# SolderIron2_0.net
KiCad netlist of a schematic drawn in EAGLE
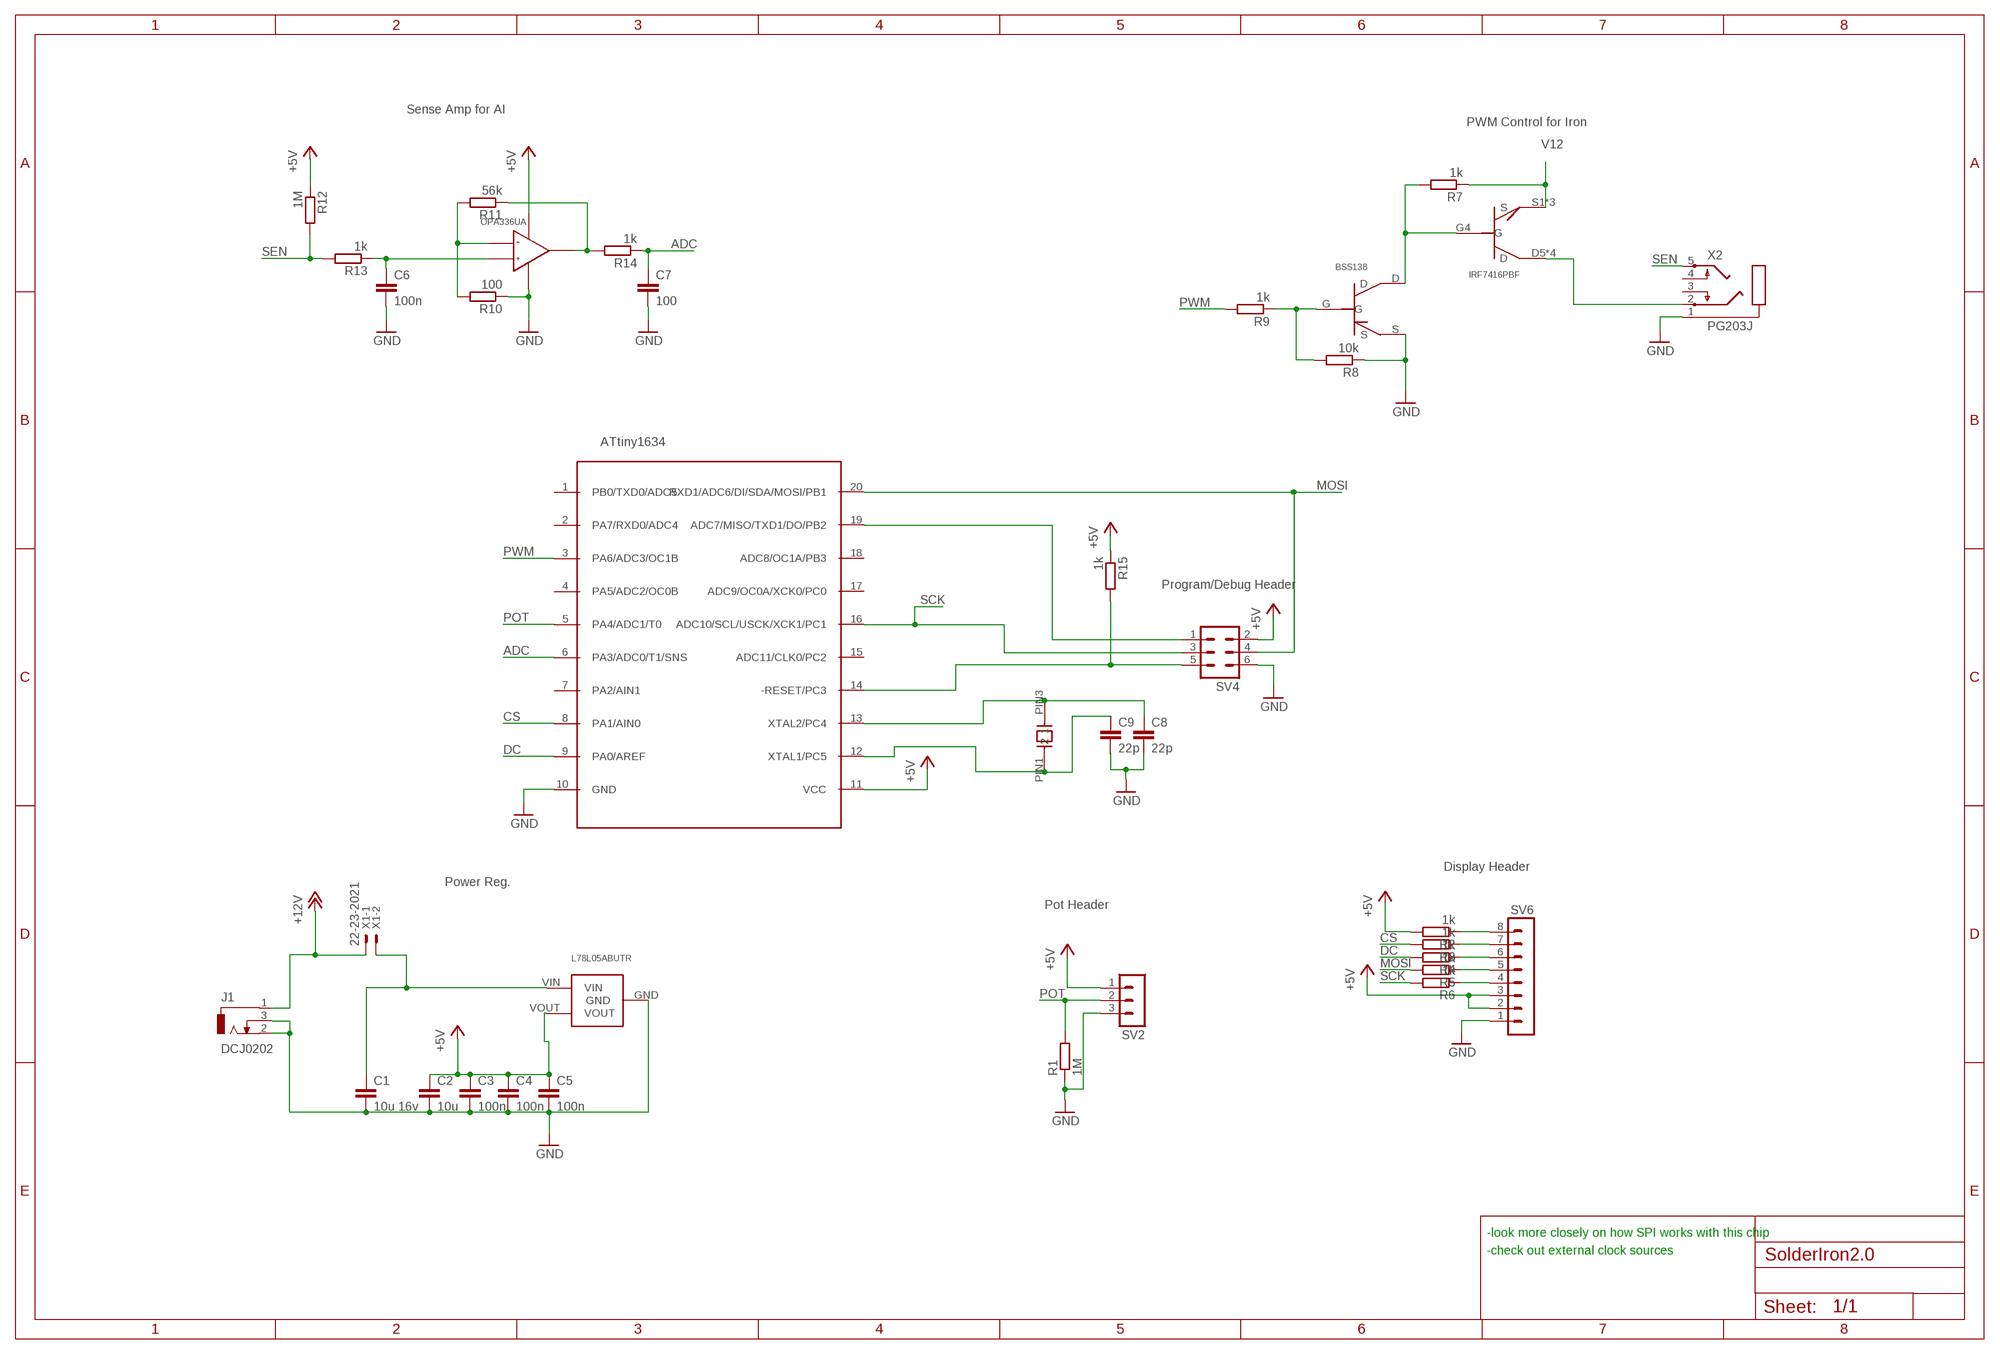
[diagram p0: schematic, sheet 1]

(export (version "E")
  (design (tool "Eeschema 10.0.6"))
  (components
    (comp (ref "C1")
      (value "10u 16v")
      (footprint "eagle-import:C1206")
      (libsource (lib "eagle-import") (part "CC1206"))
    )
    (comp (ref "C2")
      (value "10u")
      (footprint "eagle-import:C1206")
      (libsource (lib "eagle-import") (part "CC1206"))
    )
    (comp (ref "C3")
      (value "100n")
      (footprint "eagle-import:C1206")
      (libsource (lib "eagle-import") (part "CC1206"))
    )
    (comp (ref "C4")
      (value "100n")
      (footprint "eagle-import:C1206")
      (libsource (lib "eagle-import") (part "CC1206"))
    )
    (comp (ref "C5")
      (value "100n")
      (footprint "eagle-import:C1206")
      (libsource (lib "eagle-import") (part "CC1206"))
    )
    (comp (ref "C6")
      (value "100n")
      (footprint "eagle-import:C1206")
      (libsource (lib "eagle-import") (part "CC1206"))
    )
    (comp (ref "C7")
      (value "100")
      (footprint "eagle-import:C1206")
      (libsource (lib "eagle-import") (part "CC1206"))
    )
    (comp (ref "C8")
      (value "22p")
      (footprint "eagle-import:C1206")
      (libsource (lib "eagle-import") (part "CC1206"))
    )
    (comp (ref "C9")
      (value "22p")
      (footprint "eagle-import:C1206")
      (libsource (lib "eagle-import") (part "CC1206"))
    )
    (comp (ref "J1")
      (value "DCJ0202")
      (footprint "eagle-import:POWERJACK2.1MM")
      (libsource (lib "eagle-import") (part "DCJ0202"))
    )
    (comp (ref "R1")
      (value "1M")
      (footprint "eagle-import:R0603")
      (libsource (lib "eagle-import") (part "RR0603"))
    )
    (comp (ref "R2")
      (value "1k")
      (footprint "eagle-import:R0603")
      (libsource (lib "eagle-import") (part "RR0603"))
    )
    (comp (ref "R3")
      (value "1k")
      (footprint "eagle-import:R0603")
      (libsource (lib "eagle-import") (part "RR0603"))
    )
    (comp (ref "R4")
      (value "1k")
      (footprint "eagle-import:R0603")
      (libsource (lib "eagle-import") (part "RR0603"))
    )
    (comp (ref "R5")
      (value "1k")
      (footprint "eagle-import:R0603")
      (libsource (lib "eagle-import") (part "RR0603"))
    )
    (comp (ref "R6")
      (value "1k")
      (footprint "eagle-import:R0603")
      (libsource (lib "eagle-import") (part "RR0603"))
    )
    (comp (ref "R7")
      (value "1k")
      (footprint "eagle-import:R0603")
      (libsource (lib "eagle-import") (part "RR0603"))
    )
    (comp (ref "R8")
      (value "10k")
      (footprint "eagle-import:R0603")
      (libsource (lib "eagle-import") (part "RR0603"))
    )
    (comp (ref "R9")
      (value "1k")
      (footprint "eagle-import:R0603")
      (libsource (lib "eagle-import") (part "RR0603"))
    )
    (comp (ref "R10")
      (value "100")
      (footprint "eagle-import:R0603")
      (libsource (lib "eagle-import") (part "RR0603"))
    )
    (comp (ref "R11")
      (value "56k")
      (footprint "eagle-import:R0603")
      (libsource (lib "eagle-import") (part "RR0603"))
    )
    (comp (ref "R12")
      (value "1M")
      (footprint "eagle-import:R0603")
      (libsource (lib "eagle-import") (part "RR0603"))
    )
    (comp (ref "R13")
      (value "1k")
      (footprint "eagle-import:R0603")
      (libsource (lib "eagle-import") (part "RR0603"))
    )
    (comp (ref "R14")
      (value "1k")
      (footprint "eagle-import:R0603")
      (libsource (lib "eagle-import") (part "RR0603"))
    )
    (comp (ref "R15")
      (value "1k")
      (footprint "eagle-import:R0603")
      (libsource (lib "eagle-import") (part "RR0603"))
    )
    (comp (ref "SV2")
      (value "MA03-1")
      (footprint "eagle-import:MA03-1")
      (libsource (lib "eagle-import") (part "MA03-1"))
    )
    (comp (ref "SV4")
      (value "MA03-2")
      (footprint "eagle-import:MA03-2")
      (libsource (lib "eagle-import") (part "MA03-2"))
    )
    (comp (ref "SV6")
      (value "MA08-1")
      (footprint "eagle-import:MA08-1")
      (libsource (lib "eagle-import") (part "MA08-1"))
    )
    (comp (ref "U$1")
      (value "IRF7416PBF")
      (footprint "eagle-import:8-SOIC")
      (libsource (lib "eagle-import") (part "IRF7416PBF"))
    )
    (comp (ref "U$2")
      (value "L78L05ABUTR")
      (footprint "eagle-import:SOT89-3")
      (libsource (lib "eagle-import") (part "L78L05ABUTR"))
    )
    (comp (ref "U$3")
      (value "BSS138")
      (footprint "eagle-import:SOT-23")
      (libsource (lib "eagle-import") (part "BSS138"))
    )
    (comp (ref "U$4")
      (value "OPA336UA")
      (footprint "eagle-import:8-SOIC")
      (libsource (lib "eagle-import") (part "OPA336UA"))
    )
    (comp (ref "U$5")
      (value "ATTINY1634")
      (footprint "eagle-import:SOIC20")
      (libsource (lib "eagle-import") (part "ATTINY1634"))
    )
    (comp (ref "U$6")
      (value "CX3225GB12000H0KPSC1")
      (footprint "eagle-import:4-SIZ")
      (libsource (lib "eagle-import") (part "CX3225GB12000H0KPSC1"))
    )
    (comp (ref "X1")
      (value "22-23-2021")
      (footprint "eagle-import:22-23-2021")
      (fields (field (name "MF") "MOLEX"))
      (libsource (lib "eagle-import") (part "22-23-2021"))
    )
    (comp (ref "X2")
      (value "PG203J")
      (footprint "eagle-import:PG203J")
      (libsource (lib "eagle-import") (part "PG203J"))
    )
  )
  (nets
    (net (code "1") (name "+5V") (class "Default")
      (node (ref "C2") (pin "1") (pinfunction "1_1") (pintype "passive"))
      (node (ref "C3") (pin "1") (pinfunction "1_1") (pintype "passive"))
      (node (ref "C4") (pin "1") (pinfunction "1_1") (pintype "passive"))
      (node (ref "C5") (pin "1") (pinfunction "1_1") (pintype "passive"))
      (node (ref "R12") (pin "1") (pinfunction "1_1") (pintype "passive"))
      (node (ref "R15") (pin "1") (pinfunction "1_1") (pintype "passive"))
      (node (ref "R2") (pin "2") (pinfunction "2_2") (pintype "passive"))
      (node (ref "SV2") (pin "1") (pinfunction "1_1") (pintype "passive"))
      (node (ref "SV4") (pin "2") (pinfunction "2_2") (pintype "passive"))
      (node (ref "SV6") (pin "2") (pinfunction "2_2") (pintype "passive"))
      (node (ref "SV6") (pin "3") (pinfunction "3_3") (pintype "passive"))
      (node (ref "U$2") (pin "VOUT") (pinfunction "VOUT_VOUT") (pintype "bidirectional"))
      (node (ref "U$4") (pin "D7") (pinfunction "V+_D7") (pintype "bidirectional"))
      (node (ref "U$5") (pin "11") (pinfunction "VCC_11") (pintype "power_in"))
    )
    (net (code "2") (name "+12V") (class "Default")
      (node (ref "J1") (pin "1") (pinfunction "1_1") (pintype "passive"))
      (node (ref "X1") (pin "1") (pinfunction "S_1") (pintype "passive"))
    )
    (net (code "3") (name "/ADC") (class "Default")
      (node (ref "C7") (pin "1") (pinfunction "1_1") (pintype "passive"))
      (node (ref "R14") (pin "1") (pinfunction "1_1") (pintype "passive"))
      (node (ref "U$5") (pin "6") (pinfunction "PA3/ADC0/T1/SNS_6") (pintype "bidirectional"))
    )
    (net (code "4") (name "/CS") (class "Default")
      (node (ref "R3") (pin "2") (pinfunction "2_2") (pintype "passive"))
      (node (ref "U$5") (pin "8") (pinfunction "PA1/AIN0_8") (pintype "bidirectional"))
    )
    (net (code "5") (name "/DC") (class "Default")
      (node (ref "R4") (pin "2") (pinfunction "2_2") (pintype "passive"))
      (node (ref "U$5") (pin "9") (pinfunction "PA0/AREF_9") (pintype "bidirectional"))
    )
    (net (code "6") (name "/MOSI") (class "Default")
      (node (ref "R5") (pin "2") (pinfunction "2_2") (pintype "passive"))
      (node (ref "SV4") (pin "4") (pinfunction "4_4") (pintype "passive"))
      (node (ref "U$5") (pin "20") (pinfunction "RXD1/ADC6/DI/SDA/MOSI/PB1_20") (pintype "bidirectional"))
    )
    (net (code "7") (name "/POT") (class "Default")
      (node (ref "R1") (pin "2") (pinfunction "2_2") (pintype "passive"))
      (node (ref "SV2") (pin "2") (pinfunction "2_2") (pintype "passive"))
      (node (ref "U$5") (pin "5") (pinfunction "PA4/ADC1/T0_5") (pintype "bidirectional"))
    )
    (net (code "8") (name "/PWM") (class "Default")
      (node (ref "R9") (pin "2") (pinfunction "2_2") (pintype "passive"))
      (node (ref "U$5") (pin "3") (pinfunction "PA6/ADC3/OC1B_3") (pintype "bidirectional"))
    )
    (net (code "9") (name "/SCK") (class "Default")
      (node (ref "R6") (pin "2") (pinfunction "2_2") (pintype "passive"))
      (node (ref "SV4") (pin "3") (pinfunction "3_3") (pintype "passive"))
      (node (ref "U$5") (pin "16") (pinfunction "ADC10/SCL/USCK/XCK1/PC1_16") (pintype "bidirectional"))
    )
    (net (code "10") (name "/SEN") (class "Default")
      (node (ref "R12") (pin "2") (pinfunction "2_2") (pintype "passive"))
      (node (ref "R13") (pin "2") (pinfunction "2_2") (pintype "passive"))
      (node (ref "X2") (pin "5") (pinfunction "5_5") (pintype "passive"))
    )
    (net (code "11") (name "/V12") (class "Default")
      (node (ref "C1") (pin "1") (pinfunction "1_1") (pintype "passive"))
      (node (ref "R7") (pin "1") (pinfunction "1_1") (pintype "passive"))
      (node (ref "U$1") (pin "S1") (pinfunction "S_S1") (pintype "bidirectional"))
      (node (ref "U$1") (pin "S2") (pinfunction "S_S2") (pintype "bidirectional"))
      (node (ref "U$1") (pin "S3") (pinfunction "S_S3") (pintype "bidirectional"))
      (node (ref "U$2") (pin "VIN") (pinfunction "VIN_VIN") (pintype "bidirectional"))
      (node (ref "X1") (pin "2") (pinfunction "S_2") (pintype "passive"))
    )
    (net (code "12") (name "GND") (class "Default")
      (node (ref "C1") (pin "2") (pinfunction "2_2") (pintype "passive"))
      (node (ref "C2") (pin "2") (pinfunction "2_2") (pintype "passive"))
      (node (ref "C3") (pin "2") (pinfunction "2_2") (pintype "passive"))
      (node (ref "C4") (pin "2") (pinfunction "2_2") (pintype "passive"))
      (node (ref "C5") (pin "2") (pinfunction "2_2") (pintype "passive"))
      (node (ref "C6") (pin "2") (pinfunction "2_2") (pintype "passive"))
      (node (ref "C7") (pin "2") (pinfunction "2_2") (pintype "passive"))
      (node (ref "C8") (pin "2") (pinfunction "2_2") (pintype "passive"))
      (node (ref "C9") (pin "2") (pinfunction "2_2") (pintype "passive"))
      (node (ref "J1") (pin "2") (pinfunction "3_2") (pintype "passive"))
      (node (ref "J1") (pin "3") (pinfunction "2_3") (pintype "passive"))
      (node (ref "R1") (pin "1") (pinfunction "1_1") (pintype "passive"))
      (node (ref "R10") (pin "1") (pinfunction "1_1") (pintype "passive"))
      (node (ref "R8") (pin "1") (pinfunction "1_1") (pintype "passive"))
      (node (ref "SV2") (pin "3") (pinfunction "3_3") (pintype "passive"))
      (node (ref "SV4") (pin "6") (pinfunction "6_6") (pintype "passive"))
      (node (ref "SV6") (pin "1") (pinfunction "1_1") (pintype "passive"))
      (node (ref "U$2") (pin "GND") (pinfunction "GND_GND") (pintype "bidirectional"))
      (node (ref "U$3") (pin "S") (pinfunction "S_S") (pintype "bidirectional"))
      (node (ref "U$4") (pin "G4") (pinfunction "V-_G4") (pintype "bidirectional"))
      (node (ref "U$5") (pin "10") (pinfunction "GND_10") (pintype "power_in"))
      (node (ref "X2") (pin "1") (pinfunction "1_1") (pintype "passive"))
    )
    (net (code "13") (name "Net-(R2-Pad1)") (class "Default")
      (node (ref "R2") (pin "1") (pinfunction "1_1") (pintype "passive"))
      (node (ref "SV6") (pin "8") (pinfunction "8_8") (pintype "passive"))
    )
    (net (code "14") (name "Net-(R3-Pad1)") (class "Default")
      (node (ref "R3") (pin "1") (pinfunction "1_1") (pintype "passive"))
      (node (ref "SV6") (pin "7") (pinfunction "7_7") (pintype "passive"))
    )
    (net (code "15") (name "Net-(R4-Pad1)") (class "Default")
      (node (ref "R4") (pin "1") (pinfunction "1_1") (pintype "passive"))
      (node (ref "SV6") (pin "6") (pinfunction "6_6") (pintype "passive"))
    )
    (net (code "16") (name "Net-(R5-Pad1)") (class "Default")
      (node (ref "R5") (pin "1") (pinfunction "1_1") (pintype "passive"))
      (node (ref "SV6") (pin "5") (pinfunction "5_5") (pintype "passive"))
    )
    (net (code "17") (name "Net-(R6-Pad1)") (class "Default")
      (node (ref "R6") (pin "1") (pinfunction "1_1") (pintype "passive"))
      (node (ref "SV6") (pin "4") (pinfunction "4_4") (pintype "passive"))
    )
    (net (code "18") (name "Net-(R8-Pad2)") (class "Default")
      (node (ref "R8") (pin "2") (pinfunction "2_2") (pintype "passive"))
      (node (ref "R9") (pin "1") (pinfunction "1_1") (pintype "passive"))
      (node (ref "U$3") (pin "G") (pinfunction "G_G") (pintype "bidirectional"))
    )
    (net (code "19") (name "Net-(U$1-D-PadD5)") (class "Default")
      (node (ref "U$1") (pin "D5") (pinfunction "D_D5") (pintype "bidirectional"))
      (node (ref "U$1") (pin "D6") (pinfunction "D_D6") (pintype "bidirectional"))
      (node (ref "U$1") (pin "D7") (pinfunction "D_D7") (pintype "bidirectional"))
      (node (ref "U$1") (pin "D8") (pinfunction "D_D8") (pintype "bidirectional"))
      (node (ref "X2") (pin "2") (pinfunction "2_2") (pintype "passive"))
    )
    (net (code "20") (name "Net-(U$1-G)") (class "Default")
      (node (ref "R7") (pin "2") (pinfunction "2_2") (pintype "passive"))
      (node (ref "U$1") (pin "G4") (pinfunction "G_G4") (pintype "bidirectional"))
      (node (ref "U$3") (pin "D") (pinfunction "D_D") (pintype "bidirectional"))
    )
    (net (code "21") (name "Net-(U$4-IN+)") (class "Default")
      (node (ref "C6") (pin "1") (pinfunction "1_1") (pintype "passive"))
      (node (ref "R13") (pin "1") (pinfunction "1_1") (pintype "passive"))
      (node (ref "U$4") (pin "S3") (pinfunction "IN+_S3") (pintype "bidirectional"))
    )
    (net (code "22") (name "Net-(U$4-IN-)") (class "Default")
      (node (ref "R10") (pin "2") (pinfunction "2_2") (pintype "passive"))
      (node (ref "R11") (pin "2") (pinfunction "2_2") (pintype "passive"))
      (node (ref "U$4") (pin "S2") (pinfunction "IN-_S2") (pintype "bidirectional"))
    )
    (net (code "23") (name "Net-(U$4-OUTPUT)") (class "Default")
      (node (ref "R11") (pin "1") (pinfunction "1_1") (pintype "passive"))
      (node (ref "R14") (pin "2") (pinfunction "2_2") (pintype "passive"))
      (node (ref "U$4") (pin "D6") (pinfunction "OUTPUT_D6") (pintype "bidirectional"))
    )
    (net (code "24") (name "Net-(U$5--RESET{slash}PC3)") (class "Default")
      (node (ref "R15") (pin "2") (pinfunction "2_2") (pintype "passive"))
      (node (ref "SV4") (pin "5") (pinfunction "5_5") (pintype "passive"))
      (node (ref "U$5") (pin "14") (pinfunction "-RESET/PC3_14") (pintype "bidirectional"))
    )
    (net (code "25") (name "Net-(U$5-ADC7{slash}MISO{slash}TXD1{slash}DO{slash}PB2)") (class "Default")
      (node (ref "SV4") (pin "1") (pinfunction "1_1") (pintype "passive"))
      (node (ref "U$5") (pin "19") (pinfunction "ADC7/MISO/TXD1/DO/PB2_19") (pintype "bidirectional"))
    )
    (net (code "26") (name "Net-(U$5-XTAL1{slash}PC5)") (class "Default")
      (node (ref "C9") (pin "1") (pinfunction "1_1") (pintype "passive"))
      (node (ref "U$5") (pin "12") (pinfunction "XTAL1/PC5_12") (pintype "bidirectional"))
      (node (ref "U$6") (pin "PIN1") (pinfunction "1_PIN1") (pintype "bidirectional"))
    )
    (net (code "27") (name "Net-(U$5-XTAL2{slash}PC4)") (class "Default")
      (node (ref "C8") (pin "1") (pinfunction "1_1") (pintype "passive"))
      (node (ref "U$5") (pin "13") (pinfunction "XTAL2/PC4_13") (pintype "bidirectional"))
      (node (ref "U$6") (pin "PIN3") (pinfunction "2_PIN3") (pintype "bidirectional"))
    )
    (net (code "28") (name "unconnected-(U$5-ADC8{slash}OC1A{slash}PB3-Pad18)") (class "Default")
      (node (ref "U$5") (pin "18") (pinfunction "ADC8/OC1A/PB3_18") (pintype "bidirectional"))
    )
    (net (code "29") (name "unconnected-(U$5-ADC9{slash}OC0A{slash}XCK0{slash}PC0-Pad17)") (class "Default")
      (node (ref "U$5") (pin "17") (pinfunction "ADC9/OC0A/XCK0/PC0_17") (pintype "bidirectional"))
    )
    (net (code "30") (name "unconnected-(U$5-ADC11{slash}CLK0{slash}PC2-Pad15)") (class "Default")
      (node (ref "U$5") (pin "15") (pinfunction "ADC11/CLK0/PC2_15") (pintype "bidirectional"))
    )
    (net (code "31") (name "unconnected-(U$5-PA2{slash}AIN1-Pad7)") (class "Default")
      (node (ref "U$5") (pin "7") (pinfunction "PA2/AIN1_7") (pintype "bidirectional"))
    )
    (net (code "32") (name "unconnected-(U$5-PA5{slash}ADC2{slash}OC0B-Pad4)") (class "Default")
      (node (ref "U$5") (pin "4") (pinfunction "PA5/ADC2/OC0B_4") (pintype "bidirectional"))
    )
    (net (code "33") (name "unconnected-(U$5-PA7{slash}RXD0{slash}ADC4-Pad2)") (class "Default")
      (node (ref "U$5") (pin "2") (pinfunction "PA7/RXD0/ADC4_2") (pintype "bidirectional"))
    )
    (net (code "34") (name "unconnected-(U$5-PB0{slash}TXD0{slash}ADC5-Pad1)") (class "Default")
      (node (ref "U$5") (pin "1") (pinfunction "PB0/TXD0/ADC5_1") (pintype "bidirectional"))
    )
    (net (code "35") (name "unconnected-(X2-Pad3)") (class "Default")
      (node (ref "X2") (pin "3") (pinfunction "3_3") (pintype "passive"))
    )
    (net (code "36") (name "unconnected-(X2-Pad4)") (class "Default")
      (node (ref "X2") (pin "4") (pinfunction "4_4") (pintype "passive"))
    )
  )
)
